# 11-Power.net
KiCad netlist of a schematic drawn in Altium Designer
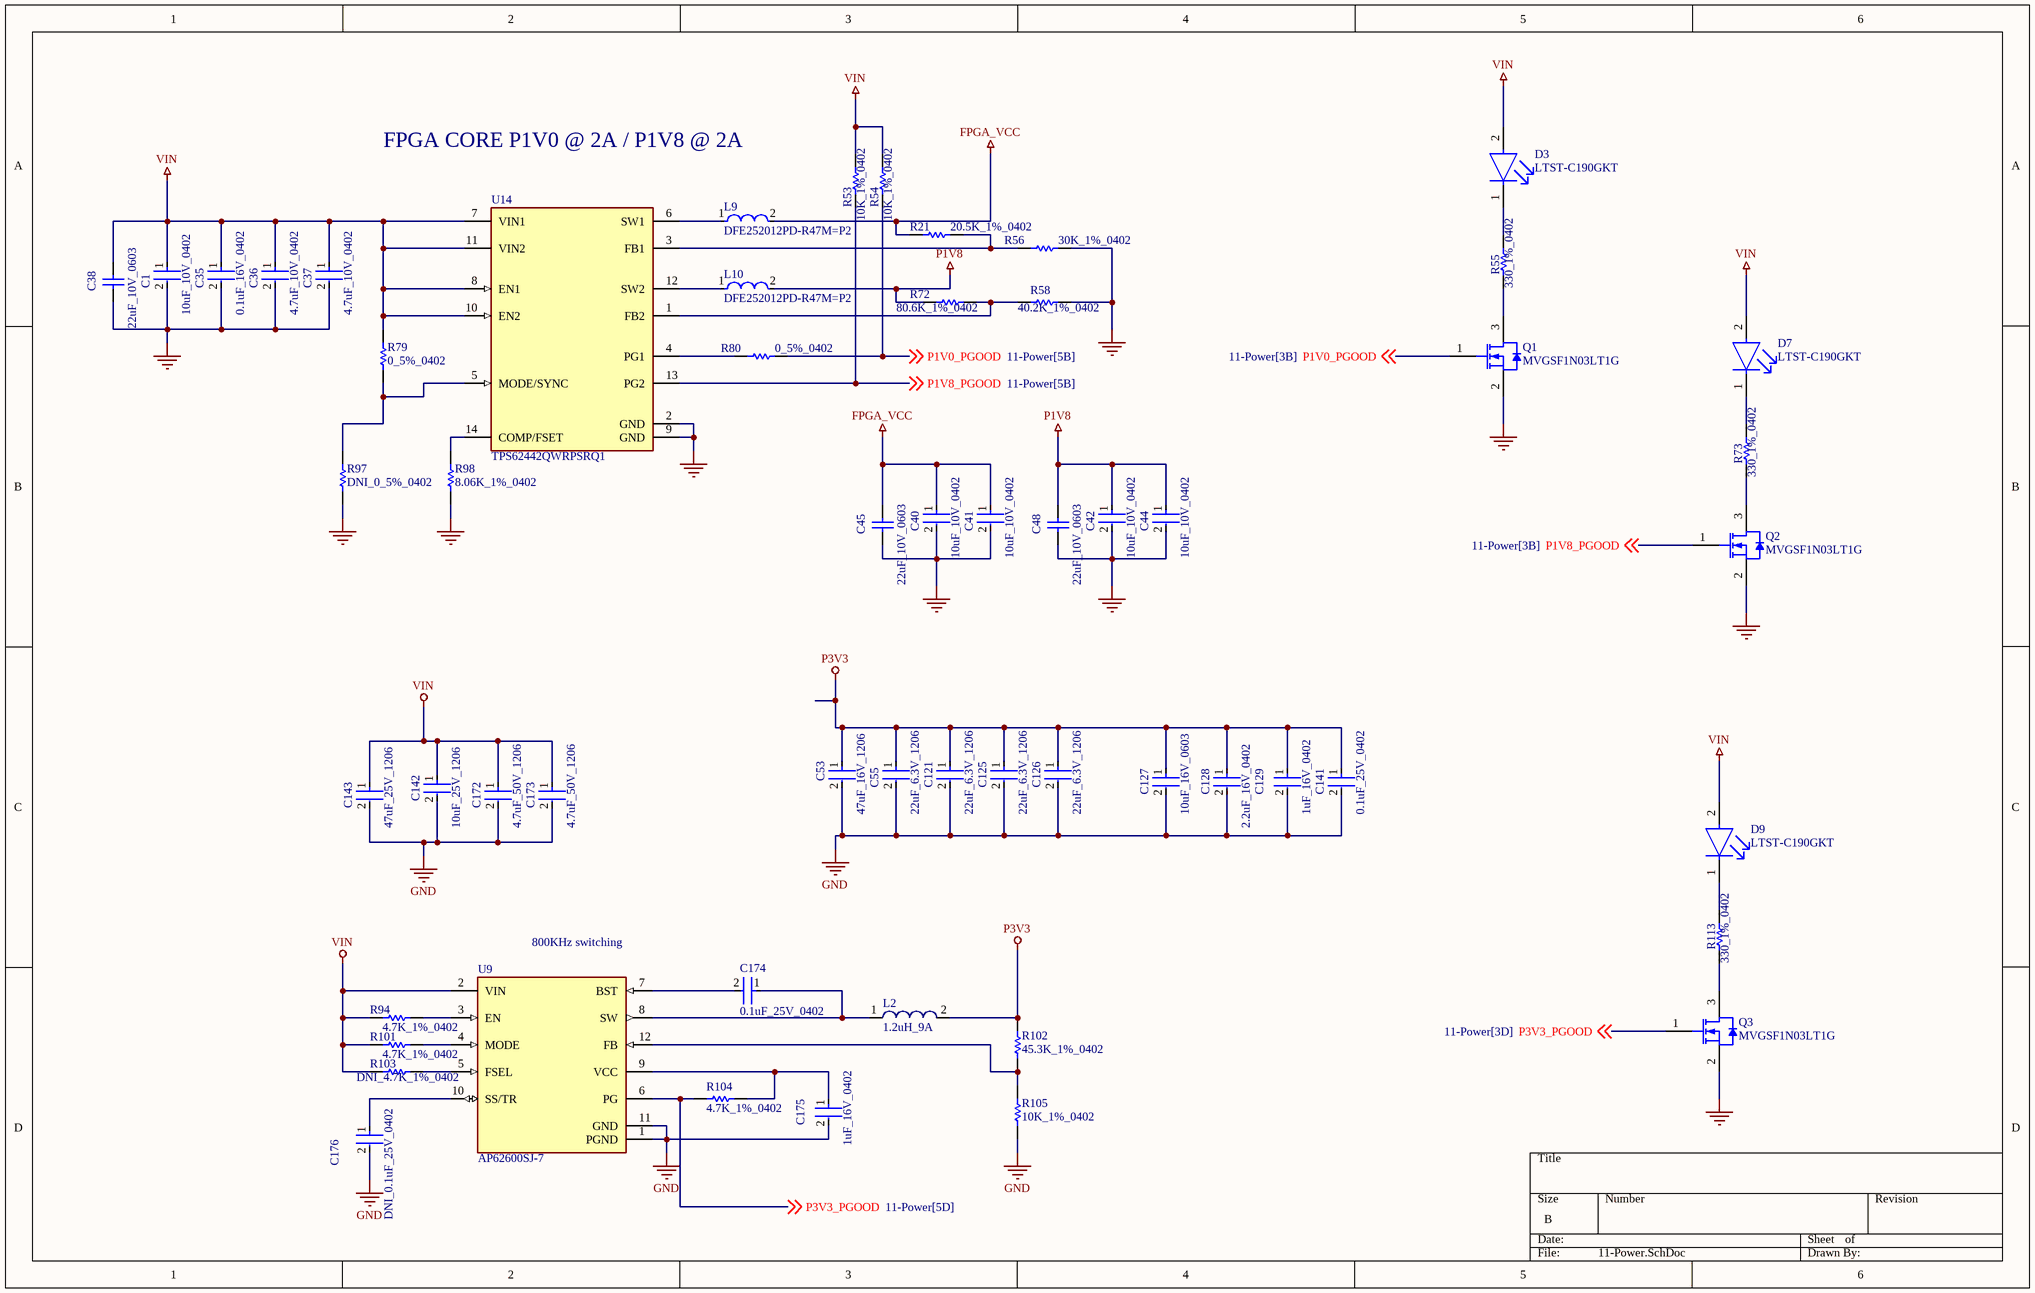
[diagram p0: 11-Power.SchDoc]

(export (version "E")
  (design (tool "Eeschema 10.0.6"))
  (components
    (comp (ref "C1")
      (value "10uF_10V_0402")
      (footprint "FP-CL05A106MP5NUNC-MFG")
      (description "CAP CER 10UF 10V X5R 0402")
      (fields
        (field (name "OCTOPART") "https://octopart.com/cl05a106mp5nunc-samsung-22457395")
        (field (name "TOLERANCE") "20%")
      )
      (libsource (lib "Altium Content Vault") (part "b4654b650e69147ec39a6b967a45e02"))
    )
    (comp (ref "C35")
      (value "0.1uF_16V_0402")
      (footprint "FP-C0402-BB-MFG")
      (description "CAP CER 0.1UF 16V 5% X7R 0402")
      (fields
        (field (name "MANUFACTURER") "Kemet")
        (field (name "MANUFACTURER PART NUMBER") "C0402C104J4RACTU")
      )
      (libsource (lib "Altium Content Vault") (part "b4654b650e69147ec39a6b967a45e02"))
    )
    (comp (ref "C36")
      (value "4.7uF_10V_0402")
      (footprint "FP-C1005-050-0_15-MFG")
      (description "CAP CER 4.7UF 10V X5R 0402")
      (fields (field (name "TOLERANCE") "10%"))
      (libsource (lib "Altium Content Vault") (part "b4654b650e69147ec39a6b967a45e02"))
    )
    (comp (ref "C37")
      (value "4.7uF_10V_0402")
      (footprint "FP-C1005-050-0_15-MFG")
      (description "CAP CER 4.7UF 10V X5R 0402")
      (fields (field (name "TOLERANCE") "10%"))
      (libsource (lib "Altium Content Vault") (part "b4654b650e69147ec39a6b967a45e02"))
    )
    (comp (ref "C38")
      (value "22uF_10V_0603")
      (footprint "CAPC1608X100X20ML10")
      (description "Chip Capacitor, 22 uF, +/- 20%, 10 V, -55 to 85 degC, 0603 (1608 Metric), RoHS, Tape and Reel")
      (fields (field (name "MANUFACTURER") "TDK") (field (name "TOLERANCE") "±20%"))
      (libsource (lib "Altium Content Vault") (part "CAP-NP-2"))
    )
    (comp (ref "C40")
      (value "10uF_10V_0402")
      (footprint "FP-CL05A106MP5NUNC-MFG")
      (description "CAP CER 10UF 10V X5R 0402")
      (fields
        (field (name "OCTOPART") "https://octopart.com/cl05a106mp5nunc-samsung-22457395")
        (field (name "TOLERANCE") "20%")
      )
      (libsource (lib "Altium Content Vault") (part "b4654b650e69147ec39a6b967a45e02"))
    )
    (comp (ref "C41")
      (value "10uF_10V_0402")
      (footprint "FP-CL05A106MP5NUNC-MFG")
      (description "CAP CER 10UF 10V X5R 0402")
      (fields
        (field (name "OCTOPART") "https://octopart.com/cl05a106mp5nunc-samsung-22457395")
        (field (name "TOLERANCE") "20%")
      )
      (libsource (lib "Altium Content Vault") (part "b4654b650e69147ec39a6b967a45e02"))
    )
    (comp (ref "C42")
      (value "10uF_10V_0402")
      (footprint "FP-CL05A106MP5NUNC-MFG")
      (description "CAP CER 10UF 10V X5R 0402")
      (fields
        (field (name "OCTOPART") "https://octopart.com/cl05a106mp5nunc-samsung-22457395")
        (field (name "TOLERANCE") "20%")
      )
      (libsource (lib "Altium Content Vault") (part "b4654b650e69147ec39a6b967a45e02"))
    )
    (comp (ref "C44")
      (value "10uF_10V_0402")
      (footprint "FP-CL05A106MP5NUNC-MFG")
      (description "CAP CER 10UF 10V X5R 0402")
      (fields
        (field (name "OCTOPART") "https://octopart.com/cl05a106mp5nunc-samsung-22457395")
        (field (name "TOLERANCE") "20%")
      )
      (libsource (lib "Altium Content Vault") (part "b4654b650e69147ec39a6b967a45e02"))
    )
    (comp (ref "C45")
      (value "22uF_10V_0603")
      (footprint "CAPC1608X100X20ML10")
      (description "Chip Capacitor, 22 uF, +/- 20%, 10 V, -55 to 85 degC, 0603 (1608 Metric), RoHS, Tape and Reel")
      (fields (field (name "MANUFACTURER") "TDK") (field (name "TOLERANCE") "±20%"))
      (libsource (lib "Altium Content Vault") (part "CAP-NP-2"))
    )
    (comp (ref "C48")
      (value "22uF_10V_0603")
      (footprint "CAPC1608X100X20ML10")
      (description "Chip Capacitor, 22 uF, +/- 20%, 10 V, -55 to 85 degC, 0603 (1608 Metric), RoHS, Tape and Reel")
      (fields (field (name "MANUFACTURER") "TDK") (field (name "TOLERANCE") "±20%"))
      (libsource (lib "Altium Content Vault") (part "CAP-NP-2"))
    )
    (comp (ref "C53")
      (value "47uF_16V_1206")
      (footprint "FP-C3216-160-0_2-MFG")
      (description "Multilayer Ceramic Capacitors 47uF ±20% 16V X5R SMD 1206")
      (fields (field (name "TOLERANCE") "20%"))
      (libsource (lib "Altium Content Vault") (part "11868f565c42a9108669ba33697ecf6"))
    )
    (comp (ref "C55")
      (value "22uF_6.3V_1206")
      (footprint "FP-1206-L_3_2_0_2-W_1_6_0-IPC_C")
      (description "General Purpose Ceramic Capacitor, 1206, 22uF, 20%, X5R, 15%, 6.3V")
      (fields (field (name "TOLERANCE") "20%") (field (name "VOLTAGE") "6.3V"))
      (libsource (lib "Altium Content Vault") (part "02cd4be3c70576c341d710602a673aa"))
    )
    (comp (ref "C121")
      (value "22uF_6.3V_1206")
      (footprint "FP-1206-L_3_2_0_2-W_1_6_0-IPC_C")
      (description "General Purpose Ceramic Capacitor, 1206, 22uF, 20%, X5R, 15%, 6.3V")
      (fields (field (name "TOLERANCE") "20%") (field (name "VOLTAGE") "6.3V"))
      (libsource (lib "Altium Content Vault") (part "02cd4be3c70576c341d710602a673aa"))
    )
    (comp (ref "C125")
      (value "22uF_6.3V_1206")
      (footprint "FP-1206-L_3_2_0_2-W_1_6_0-IPC_C")
      (description "General Purpose Ceramic Capacitor, 1206, 22uF, 20%, X5R, 15%, 6.3V")
      (fields (field (name "TOLERANCE") "20%") (field (name "VOLTAGE") "6.3V"))
      (libsource (lib "Altium Content Vault") (part "02cd4be3c70576c341d710602a673aa"))
    )
    (comp (ref "C126")
      (value "22uF_6.3V_1206")
      (footprint "FP-1206-L_3_2_0_2-W_1_6_0-IPC_C")
      (description "General Purpose Ceramic Capacitor, 1206, 22uF, 20%, X5R, 15%, 6.3V")
      (fields (field (name "TOLERANCE") "20%") (field (name "VOLTAGE") "6.3V"))
      (libsource (lib "Altium Content Vault") (part "02cd4be3c70576c341d710602a673aa"))
    )
    (comp (ref "C127")
      (value "10uF_16V_0603")
      (footprint "FP-0603-L_1_6_0_2-W_0_8_0-MFG")
      (description "Multilayer Ceramic Capacitor 10uF 16V X5R 20% SMD 0603 T/R")
      (fields (field (name "TOLERANCE") "20%"))
      (libsource (lib "Altium Content Vault") (part "b4654b650e69147ec39a6b967a45e02"))
    )
    (comp (ref "C128")
      (value "2.2uF_16V_0402")
      (footprint "FP-C1005-050-0_05-IPC_A")
      (description "Multilayer Ceramic Capacitors 2.2μF ±10% 16V X5R SMD 0402")
      (fields (field (name "TOLERANCE") "10%"))
      (libsource (lib "Altium Content Vault") (part "b4654b650e69147ec39a6b967a45e02"))
    )
    (comp (ref "C129")
      (value "1uF_16V_0402")
      (footprint "FP-0402-L_1_0_0_05-W_0_5-IPC_A")
      (description "None")
      (fields (field (name "TOLERANCE") "10%"))
      (libsource (lib "Altium Content Vault") (part "b4654b650e69147ec39a6b967a45e02"))
    )
    (comp (ref "C141")
      (value "0.1uF_25V_0402")
      (footprint "FP-0402-L_1_0_1-W_0_5_0_1-IPC_C")
      (description "General Purpose Ceramic Capacitor, 0402, 100nF, 10%, X7R, 15%, 25V")
      (fields (field (name "VOLTAGE") "25V") (field (name "TOLERANCE") "10%"))
      (libsource (lib "Altium Content Vault") (part "b4654b650e69147ec39a6b967a45e02"))
    )
    (comp (ref "C142")
      (value "10uF_25V_1206")
      (footprint "FP-1206-L_3_2_0_2-W_1_6_0-IPC_A")
      (description "General Purpose Ceramic Capacitor, 1206, 10uF, 20%, X5R, 15%, 25V")
      (fields (field (name "TOLERANCE") "20%"))
      (libsource (lib "Altium Content Vault") (part "02cd4be3c70576c341d710602a673aa"))
    )
    (comp (ref "C143")
      (value "47uF_25V_1206")
      (footprint "FP-C3216-160-0_2-MFG")
      (description "Multilayer Ceramic Capacitors 47uF ±20% 25V X5R SMD 1206")
      (fields (field (name "VOLTAGE") "25V") (field (name "TOLERANCE") "20%"))
      (libsource (lib "Altium Content Vault") (part "11868f565c42a9108669ba33697ecf6"))
    )
    (comp (ref "C172")
      (value "4.7uF_50V_1206")
      (footprint "FP-GRM31C-0_2-e0_3_0_8-IPC_C")
      (description "Chip Multilayer Ceramic Capacitors for General Purpose, 1206, 4.7uF, X7R, 15%, 10%, 50V")
      (fields (field (name "VOLTAGE") "50V") (field (name "TOLERANCE") "10%"))
      (libsource (lib "Altium Content Vault") (part "02cd4be3c70576c341d710602a673aa"))
    )
    (comp (ref "C173")
      (value "4.7uF_50V_1206")
      (footprint "FP-GRM31C-0_2-e0_3_0_8-IPC_C")
      (description "Chip Multilayer Ceramic Capacitors for General Purpose, 1206, 4.7uF, X7R, 15%, 10%, 50V")
      (fields (field (name "VOLTAGE") "50V") (field (name "TOLERANCE") "10%"))
      (libsource (lib "Altium Content Vault") (part "02cd4be3c70576c341d710602a673aa"))
    )
    (comp (ref "C174")
      (value "0.1uF_25V_0402")
      (footprint "FP-0402-L_1_0_1-W_0_5_0_1-IPC_C")
      (description "General Purpose Ceramic Capacitor, 0402, 100nF, 10%, X7R, 15%, 25V")
      (fields (field (name "VOLTAGE") "25V") (field (name "TOLERANCE") "10%"))
      (libsource (lib "Altium Content Vault") (part "b4654b650e69147ec39a6b967a45e02"))
    )
    (comp (ref "C175")
      (value "1uF_16V_0402")
      (footprint "FP-0402-L_1_0_0_05-W_0_5-IPC_A")
      (description "None")
      (fields (field (name "TOLERANCE") "10%"))
      (libsource (lib "Altium Content Vault") (part "b4654b650e69147ec39a6b967a45e02"))
    )
    (comp (ref "C176")
      (value "DNI_0.1uF_25V_0402")
      (footprint "FP-0402-L_1_0_1-W_0_5_0_1-IPC_C")
      (description "General Purpose Ceramic Capacitor, 0402, 100nF, 10%, X7R, 15%, 25V")
      (fields (field (name "VOLTAGE") "25V") (field (name "TOLERANCE") "10%"))
      (libsource (lib "Altium Content Vault") (part "b4654b650e69147ec39a6b967a45e02"))
    )
    (comp (ref "D3")
      (value "LTST-C190GKT")
      (footprint "FP-LTST-C190GKT-MFG")
      (description "LED GREEN CLEAR CHIP SMD")
      (fields (field (name "VOLTAGE") "2V"))
      (libsource (lib "Altium Content Vault") (part "8706943c75ba83719d021d2fdc84c58"))
    )
    (comp (ref "D7")
      (value "LTST-C190GKT")
      (footprint "FP-LTST-C190GKT-MFG")
      (description "LED GREEN CLEAR CHIP SMD")
      (fields (field (name "VOLTAGE") "2V"))
      (libsource (lib "Altium Content Vault") (part "8706943c75ba83719d021d2fdc84c58"))
    )
    (comp (ref "D9")
      (value "LTST-C190GKT")
      (footprint "FP-LTST-C190GKT-MFG")
      (description "LED GREEN CLEAR CHIP SMD")
      (fields (field (name "VOLTAGE") "2V"))
      (libsource (lib "Altium Content Vault") (part "8706943c75ba83719d021d2fdc84c58"))
    )
    (comp (ref "L2")
      (value "1.2uH_9A")
      (footprint "WE-LHMI 7050")
      (description "SMD Power Inductor WE-LHMI, L=1.2 µH")
      (fields (field (name "MANUFACTURER") "Wuerth Elektronik") (field (name "PARTNUMBER") "74437349012"))
      (libsource (lib "Altium Content Vault") (part "WE-IND-INDUCTOR-2"))
    )
    (comp (ref "L9")
      (value "DFE252012PD-R47M=P2")
      (footprint "FP-DFE252012C-IPC_A")
      (description "Shielded Wirewound Inductor 0.47uH 20% 4000mA 0.027Ω 1008 (2520)")
      (libsource (lib "Altium Content Vault") (part "725321dda6339637d4d059423bc1c3c"))
    )
    (comp (ref "L10")
      (value "DFE252012PD-R47M=P2")
      (footprint "FP-DFE252012C-IPC_A")
      (description "Shielded Wirewound Inductor 0.47uH 20% 4000mA 0.027Ω 1008 (2520)")
      (libsource (lib "Altium Content Vault") (part "725321dda6339637d4d059423bc1c3c"))
    )
    (comp (ref "Q1")
      (value "MVGSF1N03LT1G")
      (footprint "ONSC-SOT-23-3-318-08_V")
      (description "Power MOSFET, 30 V, 2.1 A, Single N-Channel, 3-Pin SOT-23, Pb-Free, Tape and Reel")
      (fields (field (name "MANUFACTURER") "On Semiconductor"))
      (libsource (lib "Altium Content Vault") (part "ONSC-NMOS-G1S2D3-3"))
    )
    (comp (ref "Q2")
      (value "MVGSF1N03LT1G")
      (footprint "ONSC-SOT-23-3-318-08_V")
      (description "Power MOSFET, 30 V, 2.1 A, Single N-Channel, 3-Pin SOT-23, Pb-Free, Tape and Reel")
      (fields (field (name "MANUFACTURER") "On Semiconductor"))
      (libsource (lib "Altium Content Vault") (part "ONSC-NMOS-G1S2D3-3"))
    )
    (comp (ref "Q3")
      (value "MVGSF1N03LT1G")
      (footprint "ONSC-SOT-23-3-318-08_V")
      (description "Power MOSFET, 30 V, 2.1 A, Single N-Channel, 3-Pin SOT-23, Pb-Free, Tape and Reel")
      (fields (field (name "MANUFACTURER") "On Semiconductor"))
      (libsource (lib "Altium Content Vault") (part "ONSC-NMOS-G1S2D3-3"))
    )
    (comp (ref "R21")
      (value "20.5K_1%_0402")
      (footprint "RESC1005X40X25NL10T10")
      (fields (field (name "MANUFACTURER") "Multicomp") (field (name "PART NUMBER") "MC00625W0402120K5"))
      (libsource (lib "Altium Content Vault") (part "RES"))
    )
    (comp (ref "R53")
      (value "10K_1%_0402")
      (footprint "RESC1005X40X25NL10T10")
      (fields (field (name "MANUFACTURER") "Bourns") (field (name "PART NUMBER") "CR0402-FX-1002GLF"))
      (libsource (lib "Altium Content Vault") (part "RES"))
    )
    (comp (ref "R54")
      (value "10K_1%_0402")
      (footprint "RESC1005X40X25NL10T10")
      (fields (field (name "MANUFACTURER") "Bourns") (field (name "PART NUMBER") "CR0402-FX-1002GLF"))
      (libsource (lib "Altium Content Vault") (part "RES"))
    )
    (comp (ref "R55")
      (value "330_1%_0402")
      (footprint "RESC1005X40X25NL10T10")
      (fields (field (name "MANUFACTURER") "Panasonic") (field (name "PART NUMBER") "ERA-2AED331X"))
      (libsource (lib "Altium Content Vault") (part "RES"))
    )
    (comp (ref "R56")
      (value "30K_1%_0402")
      (footprint "RESC1005X40X25ML05T05")
      (fields (field (name "PART NUMBER") "ERJ-2GEJ303X") (field (name "MANUFACTURER") "Panasonic"))
      (libsource (lib "Altium Content Vault") (part "RES"))
    )
    (comp (ref "R58")
      (value "40.2K_1%_0402")
      (footprint "RESC1005X40X25ML05T10")
      (fields (field (name "PART NUMBER") "RC0402FR-0740K2L") (field (name "MANUFACTURER") "Yageo / Phycomp"))
      (libsource (lib "Altium Content Vault") (part "RES"))
    )
    (comp (ref "R72")
      (value "80.6K_1%_0402")
      (footprint "RESC1005X40X25NL05T10")
      (fields (field (name "PART NUMBER") "RC0402FR-0780K6L") (field (name "MANUFACTURER") "Yageo / Phycomp"))
      (libsource (lib "Altium Content Vault") (part "RES"))
    )
    (comp (ref "R73")
      (value "330_1%_0402")
      (footprint "RESC1005X40X25NL10T10")
      (fields (field (name "MANUFACTURER") "Panasonic") (field (name "PART NUMBER") "ERA-2AED331X"))
      (libsource (lib "Altium Content Vault") (part "RES"))
    )
    (comp (ref "R79")
      (value "0_5%_0402")
      (footprint "RESC1005X40X25NL05T10")
      (fields (field (name "MANUFACTURER") "Panasonic") (field (name "PART NUMBER") "ERJ-U020R00X"))
      (libsource (lib "Altium Content Vault") (part "RES"))
    )
    (comp (ref "R80")
      (value "0_5%_0402")
      (footprint "RESC1005X40X25NL05T10")
      (fields (field (name "MANUFACTURER") "Panasonic") (field (name "PART NUMBER") "ERJ-U020R00X"))
      (libsource (lib "Altium Content Vault") (part "RES"))
    )
    (comp (ref "R94")
      (value "4.7K_1%_0402")
      (footprint "RESC1005X40X25NL10T10")
      (fields (field (name "MANUFACTURER") "Bourns") (field (name "PART NUMBER") "CR0402-FX-4701GLF"))
      (libsource (lib "Altium Content Vault") (part "RES"))
    )
    (comp (ref "R97")
      (value "DNI_0_5%_0402")
      (footprint "RESC1005X40X25NL05T10")
      (fields (field (name "MANUFACTURER") "Panasonic") (field (name "PART NUMBER") "ERJ-U020R00X"))
      (libsource (lib "Altium Content Vault") (part "RES"))
    )
    (comp (ref "R98")
      (value "8.06K_1%_0402")
      (footprint "RESC1005X40X25ML05T05")
      (description "Chip Resistor, 8.06 KOhm, +/- 1%, 63 mW, -55 to 155 degC, 0402 (1005 Metric), RoHS, Tape and Reel")
      (fields (field (name "PARTNUMBER") "CRCW04028K06FKED") (field (name "TOLERANCE") "1%"))
      (libsource (lib "Altium Content Vault") (part "RES-2"))
    )
    (comp (ref "R101")
      (value "4.7K_1%_0402")
      (footprint "RESC1005X40X25NL10T10")
      (fields (field (name "MANUFACTURER") "Bourns") (field (name "PART NUMBER") "CR0402-FX-4701GLF"))
      (libsource (lib "Altium Content Vault") (part "RES"))
    )
    (comp (ref "R102")
      (value "45.3K_1%_0402")
      (footprint "RESC1005X40X25ML05T10")
      (fields (field (name "PART NUMBER") "RC0402FR-0745K3L") (field (name "MANUFACTURER") "Yageo / Phycomp"))
      (libsource (lib "Altium Content Vault") (part "RES"))
    )
    (comp (ref "R103")
      (value "DNI_4.7K_1%_0402")
      (footprint "RESC1005X40X25NL10T10")
      (fields (field (name "MANUFACTURER") "Bourns") (field (name "PART NUMBER") "CR0402-FX-4701GLF"))
      (libsource (lib "Altium Content Vault") (part "RES"))
    )
    (comp (ref "R104")
      (value "4.7K_1%_0402")
      (footprint "RESC1005X40X25NL10T10")
      (fields (field (name "MANUFACTURER") "Bourns") (field (name "PART NUMBER") "CR0402-FX-4701GLF"))
      (libsource (lib "Altium Content Vault") (part "RES"))
    )
    (comp (ref "R105")
      (value "10K_1%_0402")
      (footprint "RESC1005X40X25NL10T10")
      (fields (field (name "MANUFACTURER") "Bourns") (field (name "PART NUMBER") "CR0402-FX-1002GLF"))
      (libsource (lib "Altium Content Vault") (part "RES"))
    )
    (comp (ref "R113")
      (value "330_1%_0402")
      (footprint "RESC1005X40X25NL10T10")
      (fields (field (name "MANUFACTURER") "Panasonic") (field (name "PART NUMBER") "ERA-2AED331X"))
      (libsource (lib "Altium Content Vault") (part "RES"))
    )
    (comp (ref "U9")
      (value "AP62600SJ-7")
      (footprint "FP-V-QFN2030-12_Type_A-MFG")
      (description "DCDC CONV HV BUCK,V-QFN2030-12")
      (libsource (lib "Altium Content Vault") (part "03c86ce2703f4b33b3045e94f7be521"))
    )
    (comp (ref "U14")
      (value "TPS62442QWRPSRQ1")
      (footprint "FP-RQR0014A-MFG")
      (description "Adjustable-Frequency Dual Step-Down Converter, 2.7-6V VIN, 0.6-5.5V 2A VOUT, VQFN-HR14")
      (libsource (lib "Altium Content Vault") (part "72c5b9bb22caeb688b1070b758806aa"))
    )
  )
  (nets
    (net (code "1") (name "FPGA_VCC") (class "Default")
      (node (ref "C40") (pin "1") (pinfunction "1_1") (pintype "passive"))
      (node (ref "C41") (pin "1") (pinfunction "1_1") (pintype "passive"))
      (node (ref "C45") (pin "2") (pinfunction "2_2") (pintype "passive"))
      (node (ref "L9") (pin "2") (pinfunction "2_2") (pintype "passive"))
      (node (ref "R21") (pin "1") (pinfunction "1_1") (pintype "passive"))
    )
    (net (code "2") (name "GND") (class "Default")
      (node (ref "C1") (pin "2") (pinfunction "2_2") (pintype "passive"))
      (node (ref "C121") (pin "2") (pinfunction "2_2") (pintype "passive"))
      (node (ref "C125") (pin "2") (pinfunction "2_2") (pintype "passive"))
      (node (ref "C126") (pin "2") (pinfunction "2_2") (pintype "passive"))
      (node (ref "C127") (pin "2") (pinfunction "2_2") (pintype "passive"))
      (node (ref "C128") (pin "2") (pinfunction "2_2") (pintype "passive"))
      (node (ref "C129") (pin "2") (pinfunction "2_2") (pintype "passive"))
      (node (ref "C141") (pin "2") (pinfunction "2_2") (pintype "passive"))
      (node (ref "C142") (pin "2") (pinfunction "2_2") (pintype "passive"))
      (node (ref "C143") (pin "2") (pinfunction "2_2") (pintype "passive"))
      (node (ref "C172") (pin "2") (pinfunction "2_2") (pintype "passive"))
      (node (ref "C173") (pin "2") (pinfunction "2_2") (pintype "passive"))
      (node (ref "C175") (pin "2") (pinfunction "2_2") (pintype "passive"))
      (node (ref "C176") (pin "2") (pinfunction "2_2") (pintype "passive"))
      (node (ref "C35") (pin "2") (pinfunction "2_2") (pintype "passive"))
      (node (ref "C36") (pin "2") (pinfunction "2_2") (pintype "passive"))
      (node (ref "C37") (pin "2") (pinfunction "2_2") (pintype "passive"))
      (node (ref "C38") (pin "1") (pinfunction "1_1") (pintype "passive"))
      (node (ref "C40") (pin "2") (pinfunction "2_2") (pintype "passive"))
      (node (ref "C41") (pin "2") (pinfunction "2_2") (pintype "passive"))
      (node (ref "C42") (pin "2") (pinfunction "2_2") (pintype "passive"))
      (node (ref "C44") (pin "2") (pinfunction "2_2") (pintype "passive"))
      (node (ref "C45") (pin "1") (pinfunction "1_1") (pintype "passive"))
      (node (ref "C48") (pin "1") (pinfunction "1_1") (pintype "passive"))
      (node (ref "C53") (pin "2") (pinfunction "2_2") (pintype "passive"))
      (node (ref "C55") (pin "2") (pinfunction "2_2") (pintype "passive"))
      (node (ref "Q1") (pin "2") (pinfunction "S_2") (pintype "passive"))
      (node (ref "Q2") (pin "2") (pinfunction "S_2") (pintype "passive"))
      (node (ref "Q3") (pin "2") (pinfunction "S_2") (pintype "passive"))
      (node (ref "R105") (pin "1") (pinfunction "1_1") (pintype "passive"))
      (node (ref "R56") (pin "2") (pinfunction "2_2") (pintype "passive"))
      (node (ref "R58") (pin "2") (pinfunction "2_2") (pintype "passive"))
      (node (ref "R97") (pin "1") (pinfunction "1_1") (pintype "passive"))
      (node (ref "R98") (pin "1") (pinfunction "1_1") (pintype "passive"))
      (node (ref "U14") (pin "2") (pinfunction "GND_2") (pintype "power_in"))
      (node (ref "U14") (pin "9") (pinfunction "GND_9") (pintype "power_in"))
      (node (ref "U9") (pin "1") (pinfunction "PGND_1") (pintype "power_in"))
      (node (ref "U9") (pin "11") (pinfunction "GND_11") (pintype "power_in"))
    )
    (net (code "3") (name "Net-(D3-C)") (class "Default")
      (node (ref "D3") (pin "1") (pinfunction "C_1") (pintype "passive"))
      (node (ref "R55") (pin "2") (pinfunction "2_2") (pintype "passive"))
    )
    (net (code "4") (name "Net-(D7-C)") (class "Default")
      (node (ref "D7") (pin "1") (pinfunction "C_1") (pintype "passive"))
      (node (ref "R73") (pin "2") (pinfunction "2_2") (pintype "passive"))
    )
    (net (code "5") (name "Net-(D9-C)") (class "Default")
      (node (ref "D9") (pin "1") (pinfunction "C_1") (pintype "passive"))
      (node (ref "R113") (pin "2") (pinfunction "2_2") (pintype "passive"))
    )
    (net (code "6") (name "Net-(Q1-D)") (class "Default")
      (node (ref "Q1") (pin "3") (pinfunction "D_3") (pintype "passive"))
      (node (ref "R55") (pin "1") (pinfunction "1_1") (pintype "passive"))
    )
    (net (code "7") (name "Net-(Q2-D)") (class "Default")
      (node (ref "Q2") (pin "3") (pinfunction "D_3") (pintype "passive"))
      (node (ref "R73") (pin "1") (pinfunction "1_1") (pintype "passive"))
    )
    (net (code "8") (name "Net-(Q3-D)") (class "Default")
      (node (ref "Q3") (pin "3") (pinfunction "D_3") (pintype "passive"))
      (node (ref "R113") (pin "1") (pinfunction "1_1") (pintype "passive"))
    )
    (net (code "9") (name "Net-(U9-BST)") (class "Default")
      (node (ref "C174") (pin "2") (pinfunction "2_2") (pintype "passive"))
      (node (ref "U9") (pin "7") (pinfunction "BST_7") (pintype "input"))
    )
    (net (code "10") (name "Net-(U9-EN)") (class "Default")
      (node (ref "R94") (pin "2") (pinfunction "2_2") (pintype "passive"))
      (node (ref "U9") (pin "3") (pinfunction "EN_3") (pintype "input"))
    )
    (net (code "11") (name "Net-(U9-FB)") (class "Default")
      (node (ref "R102") (pin "1") (pinfunction "1_1") (pintype "passive"))
      (node (ref "R105") (pin "2") (pinfunction "2_2") (pintype "passive"))
      (node (ref "U9") (pin "12") (pinfunction "FB_12") (pintype "input"))
    )
    (net (code "12") (name "Net-(U9-FSEL)") (class "Default")
      (node (ref "R103") (pin "2") (pinfunction "2_2") (pintype "passive"))
      (node (ref "U9") (pin "5") (pinfunction "FSEL_5") (pintype "input"))
    )
    (net (code "13") (name "Net-(U9-MODE)") (class "Default")
      (node (ref "R101") (pin "2") (pinfunction "2_2") (pintype "passive"))
      (node (ref "U9") (pin "4") (pinfunction "MODE_4") (pintype "input"))
    )
    (net (code "14") (name "Net-(U9-SS{slash}TR)") (class "Default")
      (node (ref "C176") (pin "1") (pinfunction "1_1") (pintype "passive"))
      (node (ref "U9") (pin "10") (pinfunction "SS/TR_10") (pintype "bidirectional"))
    )
    (net (code "15") (name "Net-(U9-SW)") (class "Default")
      (node (ref "C174") (pin "1") (pinfunction "1_1") (pintype "passive"))
      (node (ref "L2") (pin "1") (pinfunction "1_1") (pintype "passive"))
      (node (ref "U9") (pin "8") (pinfunction "SW_8") (pintype "output"))
    )
    (net (code "16") (name "Net-(U9-VCC)") (class "Default")
      (node (ref "C175") (pin "1") (pinfunction "1_1") (pintype "passive"))
      (node (ref "R104") (pin "1") (pinfunction "1_1") (pintype "passive"))
      (node (ref "U9") (pin "9") (pinfunction "VCC_9") (pintype "power_in"))
    )
    (net (code "17") (name "Net-(U14-COMP{slash}FSET)") (class "Default")
      (node (ref "R98") (pin "2") (pinfunction "2_2") (pintype "passive"))
      (node (ref "U14") (pin "14") (pinfunction "COMP/FSET_14") (pintype "passive"))
    )
    (net (code "18") (name "Net-(U14-FB1)") (class "Default")
      (node (ref "R21") (pin "2") (pinfunction "2_2") (pintype "passive"))
      (node (ref "R56") (pin "1") (pinfunction "1_1") (pintype "passive"))
      (node (ref "U14") (pin "3") (pinfunction "FB1_3") (pintype "passive"))
    )
    (net (code "19") (name "Net-(U14-FB2)") (class "Default")
      (node (ref "R58") (pin "1") (pinfunction "1_1") (pintype "passive"))
      (node (ref "R72") (pin "2") (pinfunction "2_2") (pintype "passive"))
      (node (ref "U14") (pin "1") (pinfunction "FB2_1") (pintype "passive"))
    )
    (net (code "20") (name "Net-(U14-MODE{slash}SYNC)") (class "Default")
      (node (ref "R79") (pin "1") (pinfunction "1_1") (pintype "passive"))
      (node (ref "R97") (pin "2") (pinfunction "2_2") (pintype "passive"))
      (node (ref "U14") (pin "5") (pinfunction "MODE/SYNC_5") (pintype "input"))
    )
    (net (code "21") (name "Net-(U14-PG1)") (class "Default")
      (node (ref "R80") (pin "1") (pinfunction "1_1") (pintype "passive"))
      (node (ref "U14") (pin "4") (pinfunction "PG1_4") (pintype "open_collector"))
    )
    (net (code "22") (name "Net-(U14-SW1)") (class "Default")
      (node (ref "L9") (pin "1") (pinfunction "1_1") (pintype "passive"))
      (node (ref "U14") (pin "6") (pinfunction "SW1_6") (pintype "passive"))
    )
    (net (code "23") (name "Net-(U14-SW2)") (class "Default")
      (node (ref "L10") (pin "1") (pinfunction "1_1") (pintype "passive"))
      (node (ref "U14") (pin "12") (pinfunction "SW2_12") (pintype "passive"))
    )
    (net (code "24") (name "P1V0_PGOOD") (class "Default")
      (node (ref "Q1") (pin "1") (pinfunction "G_1") (pintype "passive"))
      (node (ref "R54") (pin "1") (pinfunction "1_1") (pintype "passive"))
      (node (ref "R80") (pin "2") (pinfunction "2_2") (pintype "passive"))
    )
    (net (code "25") (name "P1V8") (class "Default")
      (node (ref "C42") (pin "1") (pinfunction "1_1") (pintype "passive"))
      (node (ref "C44") (pin "1") (pinfunction "1_1") (pintype "passive"))
      (node (ref "C48") (pin "2") (pinfunction "2_2") (pintype "passive"))
      (node (ref "L10") (pin "2") (pinfunction "2_2") (pintype "passive"))
      (node (ref "R72") (pin "1") (pinfunction "1_1") (pintype "passive"))
    )
    (net (code "26") (name "P1V8_PGOOD") (class "Default")
      (node (ref "Q2") (pin "1") (pinfunction "G_1") (pintype "passive"))
      (node (ref "R53") (pin "1") (pinfunction "1_1") (pintype "passive"))
      (node (ref "U14") (pin "13") (pinfunction "PG2_13") (pintype "open_collector"))
    )
    (net (code "27") (name "P3V3") (class "Default")
      (node (ref "C121") (pin "1") (pinfunction "1_1") (pintype "passive"))
      (node (ref "C125") (pin "1") (pinfunction "1_1") (pintype "passive"))
      (node (ref "C126") (pin "1") (pinfunction "1_1") (pintype "passive"))
      (node (ref "C127") (pin "1") (pinfunction "1_1") (pintype "passive"))
      (node (ref "C128") (pin "1") (pinfunction "1_1") (pintype "passive"))
      (node (ref "C129") (pin "1") (pinfunction "1_1") (pintype "passive"))
      (node (ref "C141") (pin "1") (pinfunction "1_1") (pintype "passive"))
      (node (ref "C53") (pin "1") (pinfunction "1_1") (pintype "passive"))
      (node (ref "C55") (pin "1") (pinfunction "1_1") (pintype "passive"))
      (node (ref "L2") (pin "2") (pinfunction "2_2") (pintype "passive"))
      (node (ref "R102") (pin "2") (pinfunction "2_2") (pintype "passive"))
    )
    (net (code "28") (name "P3V3_PGOOD") (class "Default")
      (node (ref "Q3") (pin "1") (pinfunction "G_1") (pintype "passive"))
      (node (ref "R104") (pin "2") (pinfunction "2_2") (pintype "passive"))
      (node (ref "U9") (pin "6") (pinfunction "PG_6") (pintype "open_collector"))
    )
    (net (code "29") (name "VIN") (class "Default")
      (node (ref "C1") (pin "1") (pinfunction "1_1") (pintype "passive"))
      (node (ref "C142") (pin "1") (pinfunction "1_1") (pintype "passive"))
      (node (ref "C143") (pin "1") (pinfunction "1_1") (pintype "passive"))
      (node (ref "C172") (pin "1") (pinfunction "1_1") (pintype "passive"))
      (node (ref "C173") (pin "1") (pinfunction "1_1") (pintype "passive"))
      (node (ref "C35") (pin "1") (pinfunction "1_1") (pintype "passive"))
      (node (ref "C36") (pin "1") (pinfunction "1_1") (pintype "passive"))
      (node (ref "C37") (pin "1") (pinfunction "1_1") (pintype "passive"))
      (node (ref "C38") (pin "2") (pinfunction "2_2") (pintype "passive"))
      (node (ref "D3") (pin "2") (pinfunction "A_2") (pintype "passive"))
      (node (ref "D7") (pin "2") (pinfunction "A_2") (pintype "passive"))
      (node (ref "D9") (pin "2") (pinfunction "A_2") (pintype "passive"))
      (node (ref "R101") (pin "1") (pinfunction "1_1") (pintype "passive"))
      (node (ref "R103") (pin "1") (pinfunction "1_1") (pintype "passive"))
      (node (ref "R53") (pin "2") (pinfunction "2_2") (pintype "passive"))
      (node (ref "R54") (pin "2") (pinfunction "2_2") (pintype "passive"))
      (node (ref "R79") (pin "2") (pinfunction "2_2") (pintype "passive"))
      (node (ref "R94") (pin "1") (pinfunction "1_1") (pintype "passive"))
      (node (ref "U14") (pin "10") (pinfunction "EN2_10") (pintype "input"))
      (node (ref "U14") (pin "11") (pinfunction "VIN2_11") (pintype "power_in"))
      (node (ref "U14") (pin "7") (pinfunction "VIN1_7") (pintype "power_in"))
      (node (ref "U14") (pin "8") (pinfunction "EN1_8") (pintype "input"))
      (node (ref "U9") (pin "2") (pinfunction "VIN_2") (pintype "power_in"))
    )
  )
)
